# Arduino_Micro_RGB_Controller.net
KiCad netlist of a schematic drawn in EAGLE
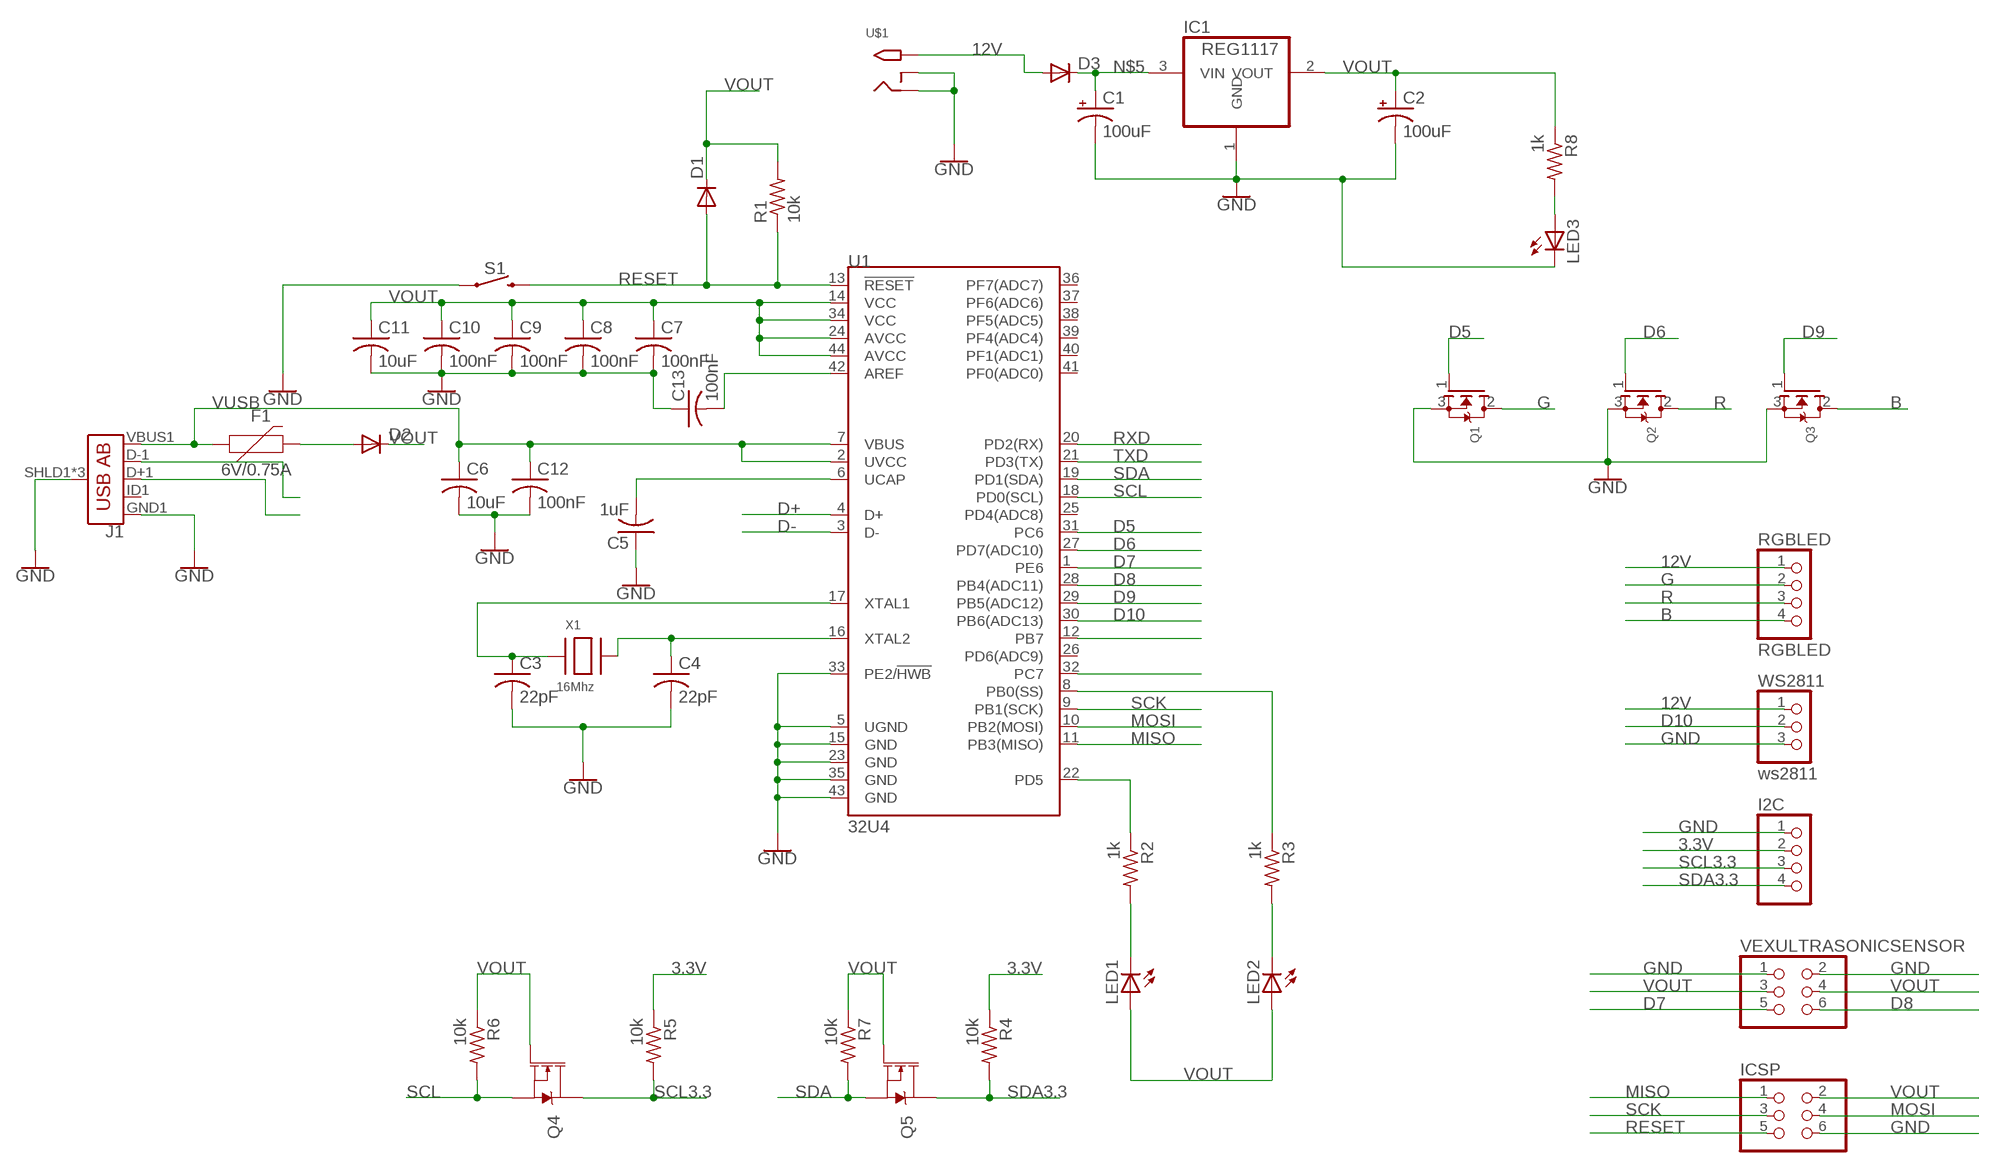
[diagram p0: schematic, sheet 1]

(export (version "E")
  (design (tool "Eeschema 10.0.6"))
  (components
    (comp (ref "C1")
      (value "100uF")
      (footprint "eagle-import:CT7343")
      (libsource (lib "eagle-import") (part "CPOL-USCT7343"))
    )
    (comp (ref "C2")
      (value "100uF")
      (footprint "eagle-import:CT7343")
      (libsource (lib "eagle-import") (part "CPOL-USCT7343"))
    )
    (comp (ref "C3")
      (value "22pF")
      (footprint "eagle-import:C0805")
      (libsource (lib "eagle-import") (part "C-USC0805"))
    )
    (comp (ref "C4")
      (value "22pF")
      (footprint "eagle-import:C0805")
      (libsource (lib "eagle-import") (part "C-USC0805"))
    )
    (comp (ref "C5")
      (value "1uF")
      (footprint "eagle-import:C0805")
      (libsource (lib "eagle-import") (part "C-USC0805"))
    )
    (comp (ref "C6")
      (value "10uF")
      (footprint "eagle-import:C0805")
      (libsource (lib "eagle-import") (part "C-USC0805"))
    )
    (comp (ref "C7")
      (value "100nF")
      (footprint "eagle-import:C0805")
      (libsource (lib "eagle-import") (part "C-USC0805"))
    )
    (comp (ref "C8")
      (value "100nF")
      (footprint "eagle-import:C0805")
      (libsource (lib "eagle-import") (part "C-USC0805"))
    )
    (comp (ref "C9")
      (value "100nF")
      (footprint "eagle-import:C0805")
      (libsource (lib "eagle-import") (part "C-USC0805"))
    )
    (comp (ref "C10")
      (value "100nF")
      (footprint "eagle-import:C0805")
      (libsource (lib "eagle-import") (part "C-USC0805"))
    )
    (comp (ref "C11")
      (value "10uF")
      (footprint "eagle-import:C0805")
      (libsource (lib "eagle-import") (part "C-USC0805"))
    )
    (comp (ref "C12")
      (value "100nF")
      (footprint "eagle-import:C0805")
      (libsource (lib "eagle-import") (part "C-USC0805"))
    )
    (comp (ref "C13")
      (value "100nF")
      (footprint "eagle-import:C0805")
      (libsource (lib "eagle-import") (part "C-USC0805"))
    )
    (comp (ref "D1")
      (value "DIODE-SOD123")
      (footprint "eagle-import:SOD123")
      (libsource (lib "eagle-import") (part "DIODE-SOD123"))
    )
    (comp (ref "D2")
      (value "DIODE-SOD123")
      (footprint "eagle-import:SOD123")
      (libsource (lib "eagle-import") (part "DIODE-SOD123"))
    )
    (comp (ref "D3")
      (value "DIODE-SOD123")
      (footprint "eagle-import:SOD123")
      (libsource (lib "eagle-import") (part "DIODE-SOD123"))
    )
    (comp (ref "F1")
      (value "6V/0.75A")
      (footprint "eagle-import:1206")
      (libsource (lib "eagle-import") (part "PPTC_THREE-QUARTER-AMP"))
    )
    (comp (ref "I2C")
      (value "PINHD-1X4")
      (footprint "eagle-import:1X04")
      (libsource (lib "eagle-import") (part "PINHD-1X4"))
    )
    (comp (ref "IC1")
      (value "REG1117")
      (footprint "eagle-import:SOT223")
      (libsource (lib "eagle-import") (part "REG1117"))
    )
    (comp (ref "ICSP")
      (value "PINHD-2X3")
      (footprint "eagle-import:2X03")
      (libsource (lib "eagle-import") (part "PINHD-2X3"))
    )
    (comp (ref "J1")
      (value "USB_AB_SMT")
      (footprint "eagle-import:USB-AB-MICRO-SMD")
      (libsource (lib "eagle-import") (part "USB_AB_SMT"))
    )
    (comp (ref "LED1")
      (value "LEDCHIPLED_0603")
      (footprint "eagle-import:CHIPLED_0603")
      (libsource (lib "eagle-import") (part "LEDCHIPLED_0603"))
    )
    (comp (ref "LED2")
      (value "LEDCHIPLED_0603")
      (footprint "eagle-import:CHIPLED_0603")
      (libsource (lib "eagle-import") (part "LEDCHIPLED_0603"))
    )
    (comp (ref "LED3")
      (value "LEDCHIPLED_0603")
      (footprint "eagle-import:CHIPLED_0603")
      (libsource (lib "eagle-import") (part "LEDCHIPLED_0603"))
    )
    (comp (ref "Q1")
      (value "MOSFET-NGDS_TO220V")
      (footprint "eagle-import:TO220V")
      (libsource (lib "eagle-import") (part "MOSFET-NGDS_TO220V"))
    )
    (comp (ref "Q2")
      (value "MOSFET-NGDS_TO220V")
      (footprint "eagle-import:TO220V")
      (libsource (lib "eagle-import") (part "MOSFET-NGDS_TO220V"))
    )
    (comp (ref "Q3")
      (value "MOSFET-NGDS_TO220V")
      (footprint "eagle-import:TO220V")
      (libsource (lib "eagle-import") (part "MOSFET-NGDS_TO220V"))
    )
    (comp (ref "Q4")
      (value "220mA/50V/3.5Ω")
      (footprint "eagle-import:SOT23-3")
      (libsource (lib "eagle-import") (part "MOSFET-NCH-BSS138"))
    )
    (comp (ref "Q5")
      (value "220mA/50V/3.5Ω")
      (footprint "eagle-import:SOT23-3")
      (libsource (lib "eagle-import") (part "MOSFET-NCH-BSS138"))
    )
    (comp (ref "R1")
      (value "10k")
      (footprint "eagle-import:M0805")
      (libsource (lib "eagle-import") (part "R-US_M0805"))
    )
    (comp (ref "R2")
      (value "1k")
      (footprint "eagle-import:M0805")
      (libsource (lib "eagle-import") (part "R-US_M0805"))
    )
    (comp (ref "R3")
      (value "1k")
      (footprint "eagle-import:M0805")
      (libsource (lib "eagle-import") (part "R-US_M0805"))
    )
    (comp (ref "R4")
      (value "10k")
      (footprint "eagle-import:M0805")
      (libsource (lib "eagle-import") (part "R-US_M0805"))
    )
    (comp (ref "R5")
      (value "10k")
      (footprint "eagle-import:M0805")
      (libsource (lib "eagle-import") (part "R-US_M0805"))
    )
    (comp (ref "R6")
      (value "10k")
      (footprint "eagle-import:M0805")
      (libsource (lib "eagle-import") (part "R-US_M0805"))
    )
    (comp (ref "R7")
      (value "10k")
      (footprint "eagle-import:M0805")
      (libsource (lib "eagle-import") (part "R-US_M0805"))
    )
    (comp (ref "R8")
      (value "1k")
      (footprint "eagle-import:M0805")
      (libsource (lib "eagle-import") (part "R-US_M0805"))
    )
    (comp (ref "RGBLED")
      (value "RGBLED")
      (footprint "eagle-import:1X04")
      (libsource (lib "eagle-import") (part "PINHD-1X4"))
    )
    (comp (ref "S1")
      (value "MOMENTARY-SWITCH-SPST-SMD-6.0X3.5MM")
      (footprint "eagle-import:TACTILE_SWITCH_SMD_6.0X3.5MM")
      (libsource (lib "eagle-import") (part "MOMENTARY-SWITCH-SPST-SMD-6.0X3.5MM"))
    )
    (comp (ref "U$1")
      (value "2.1MMJACKTHM")
      (footprint "eagle-import:PJ-102A")
      (libsource (lib "eagle-import") (part "2.1MMJACKTHM"))
    )
    (comp (ref "U1")
      (value "32U4")
      (footprint "eagle-import:TQFP44")
      (libsource (lib "eagle-import") (part "ATMEGA32U4TQFP-44"))
    )
    (comp (ref "VEXULTRASONICSENSOR")
      (value "PINHD-2X3")
      (footprint "eagle-import:2X03")
      (libsource (lib "eagle-import") (part "PINHD-2X3"))
    )
    (comp (ref "WS2811")
      (value "ws2811")
      (footprint "eagle-import:1X03")
      (libsource (lib "eagle-import") (part "PINHD-1X3"))
    )
    (comp (ref "X1")
      (value "16Mhz")
      (footprint "eagle-import:NX5032")
      (libsource (lib "eagle-import") (part "XTALNX5032"))
    )
  )
  (nets
    (net (code "1") (name "/3.3V") (class "Default")
      (node (ref "I2C") (pin "2") (pinfunction "2_2") (pintype "passive"))
      (node (ref "R4") (pin "1") (pinfunction "1_1") (pintype "passive"))
      (node (ref "R5") (pin "1") (pinfunction "1_1") (pintype "passive"))
    )
    (net (code "2") (name "/12V") (class "Default")
      (node (ref "D3") (pin "A") (pinfunction "A_A") (pintype "passive"))
      (node (ref "RGBLED") (pin "1") (pinfunction "1_1") (pintype "passive"))
      (node (ref "U$1") (pin "TIP") (pinfunction "TIP_TIP") (pintype "bidirectional"))
      (node (ref "WS2811") (pin "1") (pinfunction "1_1") (pintype "passive"))
    )
    (net (code "3") (name "/B") (class "Default")
      (node (ref "Q3") (pin "2") (pinfunction "D_2") (pintype "bidirectional"))
      (node (ref "RGBLED") (pin "4") (pinfunction "4_4") (pintype "passive"))
    )
    (net (code "4") (name "/D+") (class "Default")
      (node (ref "J1") (pin "D+1") (pinfunction "D+_D+1") (pintype "bidirectional"))
      (node (ref "U1") (pin "4") (pinfunction "D+_4") (pintype "bidirectional"))
    )
    (net (code "5") (name "/D-") (class "Default")
      (node (ref "J1") (pin "D-1") (pinfunction "D-_D-1") (pintype "bidirectional"))
      (node (ref "U1") (pin "3") (pinfunction "D-_3") (pintype "bidirectional"))
    )
    (net (code "6") (name "/D5") (class "Default")
      (node (ref "Q1") (pin "1") (pinfunction "G_1") (pintype "bidirectional"))
      (node (ref "U1") (pin "31") (pinfunction "PC6_31") (pintype "bidirectional"))
    )
    (net (code "7") (name "/D6") (class "Default")
      (node (ref "Q2") (pin "1") (pinfunction "G_1") (pintype "bidirectional"))
      (node (ref "U1") (pin "27") (pinfunction "PD7(ADC10)_27") (pintype "bidirectional"))
    )
    (net (code "8") (name "/D7") (class "Default")
      (node (ref "U1") (pin "1") (pinfunction "PE6_1") (pintype "bidirectional"))
      (node (ref "VEXULTRASONICSENSOR") (pin "5") (pinfunction "5_5") (pintype "passive"))
    )
    (net (code "9") (name "/D8") (class "Default")
      (node (ref "U1") (pin "28") (pinfunction "PB4(ADC11)_28") (pintype "bidirectional"))
      (node (ref "VEXULTRASONICSENSOR") (pin "6") (pinfunction "6_6") (pintype "passive"))
    )
    (net (code "10") (name "/D9") (class "Default")
      (node (ref "Q3") (pin "1") (pinfunction "G_1") (pintype "bidirectional"))
      (node (ref "U1") (pin "29") (pinfunction "PB5(ADC12)_29") (pintype "bidirectional"))
    )
    (net (code "11") (name "/D10") (class "Default")
      (node (ref "U1") (pin "30") (pinfunction "PB6(ADC13)_30") (pintype "bidirectional"))
      (node (ref "WS2811") (pin "2") (pinfunction "2_2") (pintype "passive"))
    )
    (net (code "12") (name "/G") (class "Default")
      (node (ref "Q1") (pin "2") (pinfunction "D_2") (pintype "bidirectional"))
      (node (ref "RGBLED") (pin "2") (pinfunction "2_2") (pintype "passive"))
    )
    (net (code "13") (name "/MISO") (class "Default")
      (node (ref "ICSP") (pin "1") (pinfunction "1_1") (pintype "passive"))
      (node (ref "U1") (pin "11") (pinfunction "PB3(MISO)_11") (pintype "bidirectional"))
    )
    (net (code "14") (name "/MOSI") (class "Default")
      (node (ref "ICSP") (pin "4") (pinfunction "4_4") (pintype "passive"))
      (node (ref "U1") (pin "10") (pinfunction "PB2(MOSI)_10") (pintype "bidirectional"))
    )
    (net (code "15") (name "/N$5") (class "Default")
      (node (ref "C1") (pin "+") (pinfunction "+_+") (pintype "passive"))
      (node (ref "D3") (pin "C") (pinfunction "C_C") (pintype "passive"))
      (node (ref "IC1") (pin "3") (pinfunction "VIN_3") (pintype "input"))
    )
    (net (code "16") (name "/R") (class "Default")
      (node (ref "Q2") (pin "2") (pinfunction "D_2") (pintype "bidirectional"))
      (node (ref "RGBLED") (pin "3") (pinfunction "3_3") (pintype "passive"))
    )
    (net (code "17") (name "/RESET") (class "Default")
      (node (ref "D1") (pin "A") (pinfunction "A_A") (pintype "passive"))
      (node (ref "ICSP") (pin "5") (pinfunction "5_5") (pintype "passive"))
      (node (ref "R1") (pin "1") (pinfunction "1_1") (pintype "passive"))
      (node (ref "S1") (pin "2") (pinfunction "2_2") (pintype "passive"))
      (node (ref "U1") (pin "13") (pinfunction "~{RESET}_13") (pintype "bidirectional"))
    )
    (net (code "18") (name "/RXD") (class "Default")
      (node (ref "U1") (pin "20") (pinfunction "PD2(RX)_20") (pintype "bidirectional"))
    )
    (net (code "19") (name "/SCK") (class "Default")
      (node (ref "ICSP") (pin "3") (pinfunction "3_3") (pintype "passive"))
      (node (ref "U1") (pin "9") (pinfunction "PB1(SCK)_9") (pintype "bidirectional"))
    )
    (net (code "20") (name "/SCL") (class "Default")
      (node (ref "Q4") (pin "2") (pinfunction "S_2") (pintype "bidirectional"))
      (node (ref "R6") (pin "2") (pinfunction "2_2") (pintype "passive"))
      (node (ref "U1") (pin "18") (pinfunction "PD0(SCL)_18") (pintype "bidirectional"))
    )
    (net (code "21") (name "/SCL3.3") (class "Default")
      (node (ref "I2C") (pin "3") (pinfunction "3_3") (pintype "passive"))
      (node (ref "Q4") (pin "3") (pinfunction "D_3") (pintype "bidirectional"))
      (node (ref "R5") (pin "2") (pinfunction "2_2") (pintype "passive"))
    )
    (net (code "22") (name "/SDA") (class "Default")
      (node (ref "Q5") (pin "2") (pinfunction "S_2") (pintype "bidirectional"))
      (node (ref "R7") (pin "2") (pinfunction "2_2") (pintype "passive"))
      (node (ref "U1") (pin "19") (pinfunction "PD1(SDA)_19") (pintype "bidirectional"))
    )
    (net (code "23") (name "/SDA3.3") (class "Default")
      (node (ref "I2C") (pin "4") (pinfunction "4_4") (pintype "passive"))
      (node (ref "Q5") (pin "3") (pinfunction "D_3") (pintype "bidirectional"))
      (node (ref "R4") (pin "2") (pinfunction "2_2") (pintype "passive"))
    )
    (net (code "24") (name "/TXD") (class "Default")
      (node (ref "U1") (pin "21") (pinfunction "PD3(TX)_21") (pintype "bidirectional"))
    )
    (net (code "25") (name "/VOUT") (class "Default")
      (node (ref "C10") (pin "1") (pinfunction "1_1") (pintype "passive"))
      (node (ref "C11") (pin "1") (pinfunction "1_1") (pintype "passive"))
      (node (ref "C2") (pin "+") (pinfunction "+_+") (pintype "passive"))
      (node (ref "C7") (pin "1") (pinfunction "1_1") (pintype "passive"))
      (node (ref "C8") (pin "1") (pinfunction "1_1") (pintype "passive"))
      (node (ref "C9") (pin "1") (pinfunction "1_1") (pintype "passive"))
      (node (ref "D1") (pin "C") (pinfunction "C_C") (pintype "passive"))
      (node (ref "D2") (pin "C") (pinfunction "C_C") (pintype "passive"))
      (node (ref "IC1") (pin "2") (pinfunction "VOUT_2") (pintype "output"))
      (node (ref "ICSP") (pin "2") (pinfunction "2_2") (pintype "passive"))
      (node (ref "LED1") (pin "A") (pinfunction "A_A") (pintype "passive"))
      (node (ref "LED2") (pin "A") (pinfunction "A_A") (pintype "passive"))
      (node (ref "Q4") (pin "1") (pinfunction "G_1") (pintype "bidirectional"))
      (node (ref "Q5") (pin "1") (pinfunction "G_1") (pintype "bidirectional"))
      (node (ref "R1") (pin "2") (pinfunction "2_2") (pintype "passive"))
      (node (ref "R6") (pin "1") (pinfunction "1_1") (pintype "passive"))
      (node (ref "R7") (pin "1") (pinfunction "1_1") (pintype "passive"))
      (node (ref "R8") (pin "1") (pinfunction "1_1") (pintype "passive"))
      (node (ref "U1") (pin "14") (pinfunction "VCC_14") (pintype "bidirectional"))
      (node (ref "U1") (pin "24") (pinfunction "AVCC_24") (pintype "bidirectional"))
      (node (ref "U1") (pin "34") (pinfunction "VCC_34") (pintype "bidirectional"))
      (node (ref "U1") (pin "44") (pinfunction "AVCC_44") (pintype "bidirectional"))
      (node (ref "VEXULTRASONICSENSOR") (pin "3") (pinfunction "3_3") (pintype "passive"))
      (node (ref "VEXULTRASONICSENSOR") (pin "4") (pinfunction "4_4") (pintype "passive"))
    )
    (net (code "26") (name "/VUSB") (class "Default")
      (node (ref "C12") (pin "1") (pinfunction "1_1") (pintype "passive"))
      (node (ref "C6") (pin "1") (pinfunction "1_1") (pintype "passive"))
      (node (ref "F1") (pin "1") (pinfunction "1_1") (pintype "bidirectional"))
      (node (ref "J1") (pin "VBUS1") (pinfunction "VBUS_VBUS1") (pintype "power_in"))
      (node (ref "U1") (pin "2") (pinfunction "UVCC_2") (pintype "bidirectional"))
      (node (ref "U1") (pin "7") (pinfunction "VBUS_7") (pintype "bidirectional"))
    )
    (net (code "27") (name "GND") (class "Default")
      (node (ref "C1") (pin "-") (pinfunction "-_-") (pintype "passive"))
      (node (ref "C10") (pin "2") (pinfunction "2_2") (pintype "passive"))
      (node (ref "C11") (pin "2") (pinfunction "2_2") (pintype "passive"))
      (node (ref "C12") (pin "2") (pinfunction "2_2") (pintype "passive"))
      (node (ref "C13") (pin "1") (pinfunction "1_1") (pintype "passive"))
      (node (ref "C2") (pin "-") (pinfunction "-_-") (pintype "passive"))
      (node (ref "C3") (pin "2") (pinfunction "2_2") (pintype "passive"))
      (node (ref "C4") (pin "2") (pinfunction "2_2") (pintype "passive"))
      (node (ref "C5") (pin "1") (pinfunction "1_1") (pintype "passive"))
      (node (ref "C6") (pin "2") (pinfunction "2_2") (pintype "passive"))
      (node (ref "C7") (pin "2") (pinfunction "2_2") (pintype "passive"))
      (node (ref "C8") (pin "2") (pinfunction "2_2") (pintype "passive"))
      (node (ref "C9") (pin "2") (pinfunction "2_2") (pintype "passive"))
      (node (ref "I2C") (pin "1") (pinfunction "1_1") (pintype "passive"))
      (node (ref "IC1") (pin "1") (pinfunction "GND_1") (pintype "power_in"))
      (node (ref "ICSP") (pin "6") (pinfunction "6_6") (pintype "passive"))
      (node (ref "J1") (pin "GND1") (pinfunction "GND_GND1") (pintype "power_in"))
      (node (ref "J1") (pin "SHLD1") (pinfunction "SHIELD_SHLD1") (pintype "bidirectional"))
      (node (ref "J1") (pin "SHLD2") (pinfunction "SHIELD_SHLD2") (pintype "bidirectional"))
      (node (ref "J1") (pin "SHLD3") (pinfunction "SHIELD_SHLD3") (pintype "bidirectional"))
      (node (ref "LED3") (pin "C") (pinfunction "C_C") (pintype "passive"))
      (node (ref "Q1") (pin "3") (pinfunction "S_3") (pintype "bidirectional"))
      (node (ref "Q2") (pin "3") (pinfunction "S_3") (pintype "bidirectional"))
      (node (ref "Q3") (pin "3") (pinfunction "S_3") (pintype "bidirectional"))
      (node (ref "S1") (pin "1") (pinfunction "1_1") (pintype "passive"))
      (node (ref "U$1") (pin "RING") (pinfunction "RING_RING") (pintype "bidirectional"))
      (node (ref "U$1") (pin "RING_SW") (pinfunction "RING_SW_RING_SW") (pintype "bidirectional"))
      (node (ref "U1") (pin "15") (pinfunction "GND_15") (pintype "bidirectional"))
      (node (ref "U1") (pin "23") (pinfunction "GND_23") (pintype "bidirectional"))
      (node (ref "U1") (pin "33") (pinfunction "PE2/~{HWB}_33") (pintype "bidirectional"))
      (node (ref "U1") (pin "35") (pinfunction "GND_35") (pintype "bidirectional"))
      (node (ref "U1") (pin "43") (pinfunction "GND_43") (pintype "bidirectional"))
      (node (ref "U1") (pin "5") (pinfunction "UGND_5") (pintype "bidirectional"))
      (node (ref "VEXULTRASONICSENSOR") (pin "1") (pinfunction "1_1") (pintype "passive"))
      (node (ref "VEXULTRASONICSENSOR") (pin "2") (pinfunction "2_2") (pintype "passive"))
      (node (ref "WS2811") (pin "3") (pinfunction "3_3") (pintype "passive"))
    )
    (net (code "28") (name "Net-(D2-PadA)") (class "Default")
      (node (ref "D2") (pin "A") (pinfunction "A_A") (pintype "passive"))
      (node (ref "F1") (pin "2") (pinfunction "2_2") (pintype "bidirectional"))
    )
    (net (code "29") (name "Net-(LED1-PadC)") (class "Default")
      (node (ref "LED1") (pin "C") (pinfunction "C_C") (pintype "passive"))
      (node (ref "R2") (pin "2") (pinfunction "2_2") (pintype "passive"))
    )
    (net (code "30") (name "Net-(LED2-PadC)") (class "Default")
      (node (ref "LED2") (pin "C") (pinfunction "C_C") (pintype "passive"))
      (node (ref "R3") (pin "2") (pinfunction "2_2") (pintype "passive"))
    )
    (net (code "31") (name "Net-(LED3-PadA)") (class "Default")
      (node (ref "LED3") (pin "A") (pinfunction "A_A") (pintype "passive"))
      (node (ref "R8") (pin "2") (pinfunction "2_2") (pintype "passive"))
    )
    (net (code "32") (name "Net-(U1-AREF)") (class "Default")
      (node (ref "C13") (pin "2") (pinfunction "2_2") (pintype "passive"))
      (node (ref "U1") (pin "42") (pinfunction "AREF_42") (pintype "bidirectional"))
    )
    (net (code "33") (name "Net-(U1-PB0(SS))") (class "Default")
      (node (ref "R3") (pin "1") (pinfunction "1_1") (pintype "passive"))
      (node (ref "U1") (pin "8") (pinfunction "PB0(SS)_8") (pintype "bidirectional"))
    )
    (net (code "34") (name "Net-(U1-PD5)") (class "Default")
      (node (ref "R2") (pin "1") (pinfunction "1_1") (pintype "passive"))
      (node (ref "U1") (pin "22") (pinfunction "PD5_22") (pintype "bidirectional"))
    )
    (net (code "35") (name "Net-(U1-UCAP)") (class "Default")
      (node (ref "C5") (pin "2") (pinfunction "2_2") (pintype "passive"))
      (node (ref "U1") (pin "6") (pinfunction "UCAP_6") (pintype "bidirectional"))
    )
    (net (code "36") (name "Net-(U1-XTAL1)") (class "Default")
      (node (ref "C3") (pin "1") (pinfunction "1_1") (pintype "passive"))
      (node (ref "U1") (pin "17") (pinfunction "XTAL1_17") (pintype "bidirectional"))
      (node (ref "X1") (pin "P$1") (pinfunction "P$1_P$1") (pintype "bidirectional"))
    )
    (net (code "37") (name "Net-(U1-XTAL2)") (class "Default")
      (node (ref "C4") (pin "1") (pinfunction "1_1") (pintype "passive"))
      (node (ref "U1") (pin "16") (pinfunction "XTAL2_16") (pintype "bidirectional"))
      (node (ref "X1") (pin "P$2") (pinfunction "P$2_P$2") (pintype "bidirectional"))
    )
    (net (code "38") (name "unconnected-(J1-USBID-PadID1)") (class "Default")
      (node (ref "J1") (pin "ID1") (pinfunction "USBID_ID1") (pintype "bidirectional"))
    )
    (net (code "39") (name "unconnected-(U1-PB7-Pad12)") (class "Default")
      (node (ref "U1") (pin "12") (pinfunction "PB7_12") (pintype "bidirectional"))
    )
    (net (code "40") (name "unconnected-(U1-PC7-Pad32)") (class "Default")
      (node (ref "U1") (pin "32") (pinfunction "PC7_32") (pintype "bidirectional"))
    )
    (net (code "41") (name "unconnected-(U1-PD4(ADC8)-Pad25)") (class "Default")
      (node (ref "U1") (pin "25") (pinfunction "PD4(ADC8)_25") (pintype "bidirectional"))
    )
    (net (code "42") (name "unconnected-(U1-PD6(ADC9)-Pad26)") (class "Default")
      (node (ref "U1") (pin "26") (pinfunction "PD6(ADC9)_26") (pintype "bidirectional"))
    )
    (net (code "43") (name "unconnected-(U1-PF0(ADC0)-Pad41)") (class "Default")
      (node (ref "U1") (pin "41") (pinfunction "PF0(ADC0)_41") (pintype "bidirectional"))
    )
    (net (code "44") (name "unconnected-(U1-PF1(ADC1)-Pad40)") (class "Default")
      (node (ref "U1") (pin "40") (pinfunction "PF1(ADC1)_40") (pintype "bidirectional"))
    )
    (net (code "45") (name "unconnected-(U1-PF4(ADC4)-Pad39)") (class "Default")
      (node (ref "U1") (pin "39") (pinfunction "PF4(ADC4)_39") (pintype "bidirectional"))
    )
    (net (code "46") (name "unconnected-(U1-PF5(ADC5)-Pad38)") (class "Default")
      (node (ref "U1") (pin "38") (pinfunction "PF5(ADC5)_38") (pintype "bidirectional"))
    )
    (net (code "47") (name "unconnected-(U1-PF6(ADC6)-Pad37)") (class "Default")
      (node (ref "U1") (pin "37") (pinfunction "PF6(ADC6)_37") (pintype "bidirectional"))
    )
    (net (code "48") (name "unconnected-(U1-PF7(ADC7)-Pad36)") (class "Default")
      (node (ref "U1") (pin "36") (pinfunction "PF7(ADC7)_36") (pintype "bidirectional"))
    )
  )
)
